# temperature.net
KiCad netlist of a schematic drawn in EAGLE
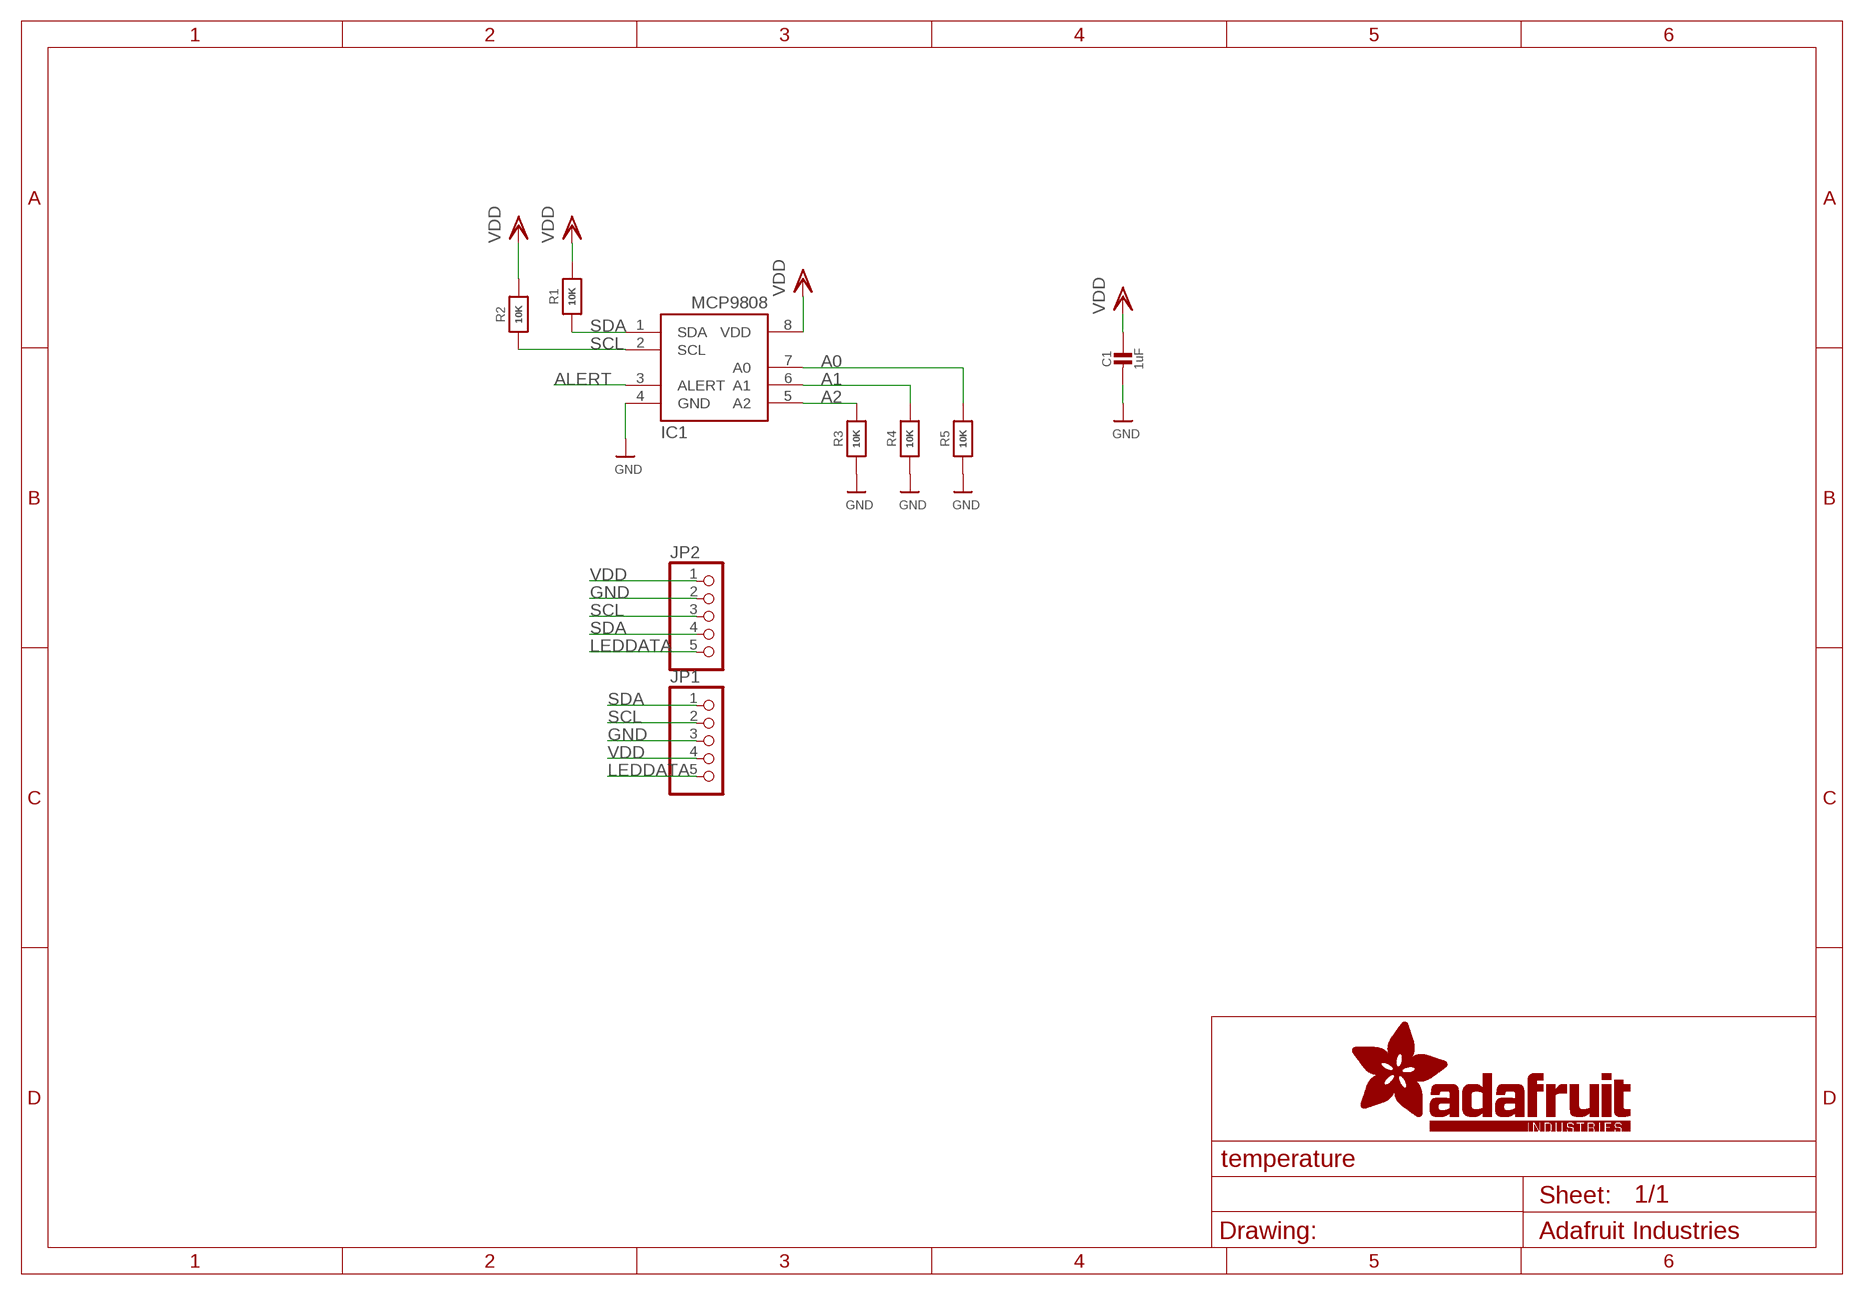
[diagram p0: schematic, sheet 1]

(export (version "E")
  (design (tool "Eeschema 10.0.6"))
  (components
    (comp (ref "C1")
      (value "1uF")
      (footprint "eagle-import:_0805MP")
      (libsource (lib "eagle-import") (part "CAP_CERAMIC_0805MP"))
    )
    (comp (ref "IC1")
      (value "MCP9808-E/MS")
      (footprint "eagle-import:MSOP8_0.65MM")
      (libsource (lib "eagle-import") (part "MCP9808-E/MS"))
    )
    (comp (ref "JP1")
      (value "PINHD-1X55X2MM")
      (footprint "eagle-import:1_05X2MM")
      (libsource (lib "eagle-import") (part "PINHD-1X55X2MM"))
    )
    (comp (ref "JP2")
      (value "PINHD-1X55X2MM")
      (footprint "eagle-import:1_05X2MM")
      (libsource (lib "eagle-import") (part "PINHD-1X55X2MM"))
    )
    (comp (ref "R1")
      (value "10K")
      (footprint "eagle-import:0805-NO")
      (libsource (lib "eagle-import") (part "RESISTOR0805_NOOUTLINE"))
    )
    (comp (ref "R2")
      (value "10K")
      (footprint "eagle-import:0805-NO")
      (libsource (lib "eagle-import") (part "RESISTOR0805_NOOUTLINE"))
    )
    (comp (ref "R3")
      (value "10K")
      (footprint "eagle-import:0805-NO")
      (libsource (lib "eagle-import") (part "RESISTOR0805_NOOUTLINE"))
    )
    (comp (ref "R4")
      (value "10K")
      (footprint "eagle-import:0805-NO")
      (libsource (lib "eagle-import") (part "RESISTOR0805_NOOUTLINE"))
    )
    (comp (ref "R5")
      (value "10K")
      (footprint "eagle-import:0805-NO")
      (libsource (lib "eagle-import") (part "RESISTOR0805_NOOUTLINE"))
    )
  )
  (nets
    (net (code "1") (name "/A0") (class "Default")
      (node (ref "IC1") (pin "7") (pinfunction "A0_7") (pintype "input"))
      (node (ref "R5") (pin "2") (pinfunction "2_2") (pintype "passive"))
    )
    (net (code "2") (name "/A1") (class "Default")
      (node (ref "IC1") (pin "6") (pinfunction "A1_6") (pintype "input"))
      (node (ref "R4") (pin "2") (pinfunction "2_2") (pintype "passive"))
    )
    (net (code "3") (name "/A2") (class "Default")
      (node (ref "IC1") (pin "5") (pinfunction "A2_5") (pintype "input"))
      (node (ref "R3") (pin "2") (pinfunction "2_2") (pintype "passive"))
    )
    (net (code "4") (name "/ALERT") (class "Default")
      (node (ref "IC1") (pin "3") (pinfunction "ALERT_3") (pintype "open_collector"))
    )
    (net (code "5") (name "/LEDDATA") (class "Default")
      (node (ref "JP1") (pin "5") (pinfunction "5_5") (pintype "passive"))
      (node (ref "JP2") (pin "5") (pinfunction "5_5") (pintype "passive"))
    )
    (net (code "6") (name "/SCL") (class "Default")
      (node (ref "IC1") (pin "2") (pinfunction "SCL_2") (pintype "bidirectional"))
      (node (ref "JP1") (pin "2") (pinfunction "2_2") (pintype "passive"))
      (node (ref "JP2") (pin "3") (pinfunction "3_3") (pintype "passive"))
      (node (ref "R2") (pin "1") (pinfunction "1_1") (pintype "passive"))
    )
    (net (code "7") (name "/SDA") (class "Default")
      (node (ref "IC1") (pin "1") (pinfunction "SDA_1") (pintype "bidirectional"))
      (node (ref "JP1") (pin "1") (pinfunction "1_1") (pintype "passive"))
      (node (ref "JP2") (pin "4") (pinfunction "4_4") (pintype "passive"))
      (node (ref "R1") (pin "1") (pinfunction "1_1") (pintype "passive"))
    )
    (net (code "8") (name "GND") (class "Default")
      (node (ref "C1") (pin "2") (pinfunction "2_2") (pintype "passive"))
      (node (ref "IC1") (pin "4") (pinfunction "GND_4") (pintype "power_in"))
      (node (ref "JP1") (pin "3") (pinfunction "3_3") (pintype "passive"))
      (node (ref "JP2") (pin "2") (pinfunction "2_2") (pintype "passive"))
      (node (ref "R3") (pin "1") (pinfunction "1_1") (pintype "passive"))
      (node (ref "R4") (pin "1") (pinfunction "1_1") (pintype "passive"))
      (node (ref "R5") (pin "1") (pinfunction "1_1") (pintype "passive"))
    )
    (net (code "9") (name "VDD") (class "Default")
      (node (ref "C1") (pin "1") (pinfunction "1_1") (pintype "passive"))
      (node (ref "IC1") (pin "8") (pinfunction "VDD_8") (pintype "power_in"))
      (node (ref "JP1") (pin "4") (pinfunction "4_4") (pintype "passive"))
      (node (ref "JP2") (pin "1") (pinfunction "1_1") (pintype "passive"))
      (node (ref "R1") (pin "2") (pinfunction "2_2") (pintype "passive"))
      (node (ref "R2") (pin "2") (pinfunction "2_2") (pintype "passive"))
    )
  )
)
